# Modbus_RTU.net
KiCad netlist of a schematic drawn in Altium Designer
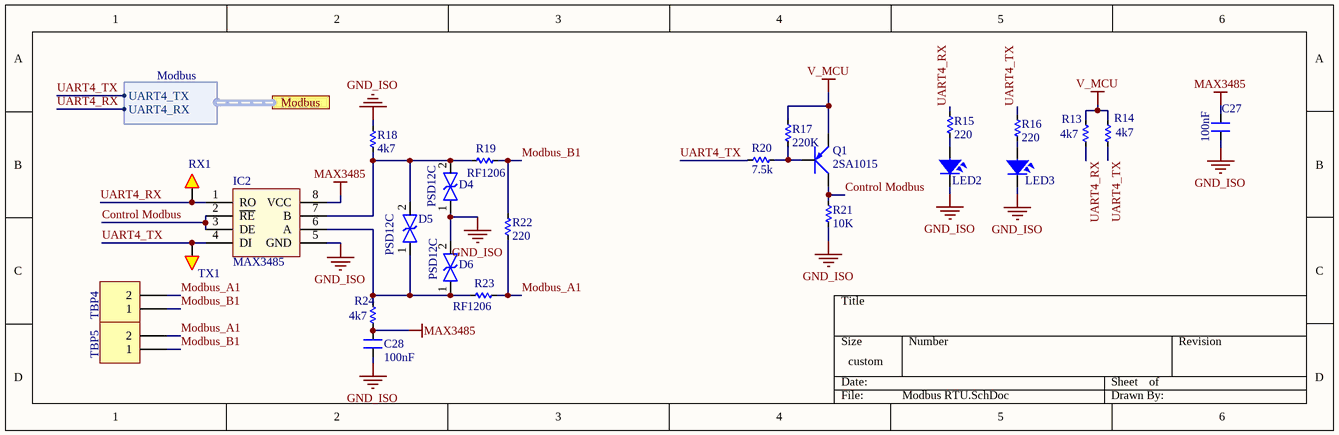
[diagram p0: Modbus RTU.SchDoc]

(export (version "E")
  (design (tool "Eeschema 10.0.6"))
  (components
    (comp (ref "B3")
      (value "RX1")
      (footprint "Test")
      (description "WR-PHD 2.54 mm Angled Socket Header")
      (fields
        (field (name "MANUFACTURER") "Würth Elektronik eiSos GmbH")
        (field (name "PARTNO") "613002143121")
        (field (name "CREATED BY") "Karrer Zheng")
      )
      (libsource (lib "Nichietsuvn") (part "Test"))
    )
    (comp (ref "B4")
      (value "TX1")
      (footprint "Test")
      (description "WR-PHD 2.54 mm Angled Socket Header")
      (fields
        (field (name "MANUFACTURER") "Würth Elektronik eiSos GmbH")
        (field (name "PARTNO") "613002143121")
        (field (name "CREATED BY") "Karrer Zheng")
      )
      (libsource (lib "Nichietsuvn") (part "Test"))
    )
    (comp (ref "C27") (value "100nF") (footprint "CN-SMD-0603") (libsource (lib "thu vien 3d") (part "CN")))
    (comp (ref "C28") (value "100nF") (footprint "CN-SMD-0603") (libsource (lib "thu vien 3d") (part "CN")))
    (comp (ref "D4")
      (value "PSD12C")
      (footprint "PSD12C")
      (description "diode tvs")
      (libsource (lib "Nichietsuvn") (part "PSD12C"))
    )
    (comp (ref "D5")
      (value "PSD12C")
      (footprint "PSD12C")
      (description "diode tvs")
      (libsource (lib "Nichietsuvn") (part "PSD12C"))
    )
    (comp (ref "D6")
      (value "PSD12C")
      (footprint "PSD12C")
      (description "diode tvs")
      (libsource (lib "Nichietsuvn") (part "PSD12C"))
    )
    (comp (ref "IC2")
      (value "MAX3485")
      (footprint "SO8")
      (description "RS232 - RS485 (Same sn75176)")
      (libsource (lib "thu vien 3d") (part "MAX485"))
    )
    (comp (ref "LED2")
      (value "LED")
      (footprint "LED-0805-Blue")
      (libsource (lib "thu vien 3d") (part "LED SMD"))
    )
    (comp (ref "LED3")
      (value "LED")
      (footprint "LED-0805-Blue")
      (libsource (lib "thu vien 3d") (part "LED SMD"))
    )
    (comp (ref "Q1")
      (value "2SA1015")
      (footprint "SOT23-321")
      (description "PNP 600mW, ECB")
      (libsource (lib "thu vien 3d") (part "2SA1015"))
    )
    (comp (ref "R13")
      (value "4k7")
      (footprint "RES-SMD-0603")
      (description "Resistor")
      (fields
        (field (name "MANUFACTURER") "Generic Components")
        (field (name "PUBLISHER") "Altium Hobart Technology Centre")
      )
      (libsource (lib "thu vien 3d") (part "Res-SMD"))
    )
    (comp (ref "R14")
      (value "4k7")
      (footprint "RES-SMD-0603")
      (description "Resistor")
      (fields
        (field (name "MANUFACTURER") "Generic Components")
        (field (name "PUBLISHER") "Altium Hobart Technology Centre")
      )
      (libsource (lib "thu vien 3d") (part "Res-SMD"))
    )
    (comp (ref "R15")
      (value "220")
      (footprint "RES-SMD-0603")
      (description "Resistor")
      (fields
        (field (name "MANUFACTURER") "Generic Components")
        (field (name "PUBLISHER") "Altium Hobart Technology Centre")
      )
      (libsource (lib "thu vien 3d") (part "Res-SMD"))
    )
    (comp (ref "R16")
      (value "220")
      (footprint "RES-SMD-0603")
      (description "Resistor")
      (fields
        (field (name "MANUFACTURER") "Generic Components")
        (field (name "PUBLISHER") "Altium Hobart Technology Centre")
      )
      (libsource (lib "thu vien 3d") (part "Res-SMD"))
    )
    (comp (ref "R17")
      (value "220K")
      (footprint "RES-SMD-0603")
      (description "Resistor")
      (fields
        (field (name "MANUFACTURER") "Generic Components")
        (field (name "PUBLISHER") "Altium Hobart Technology Centre")
      )
      (libsource (lib "thu vien 3d") (part "Res-SMD"))
    )
    (comp (ref "R18")
      (value "4k7")
      (footprint "RES-SMD-0603")
      (description "Resistor")
      (fields
        (field (name "MANUFACTURER") "Generic Components")
        (field (name "PUBLISHER") "Altium Hobart Technology Centre")
      )
      (libsource (lib "thu vien 3d") (part "Res-SMD"))
    )
    (comp (ref "R19")
      (value "RF1206")
      (footprint "RES-SMD-1206")
      (description "Resistor")
      (fields
        (field (name "MANUFACTURER") "Generic Components")
        (field (name "PUBLISHER") "Altium Hobart Technology Centre")
      )
      (libsource (lib "thu vien 3d") (part "Res-SMD"))
    )
    (comp (ref "R20")
      (value "7.5k")
      (footprint "RES-SMD-0603")
      (description "Resistor")
      (fields
        (field (name "MANUFACTURER") "Generic Components")
        (field (name "PUBLISHER") "Altium Hobart Technology Centre")
      )
      (libsource (lib "thu vien 3d") (part "Res-SMD"))
    )
    (comp (ref "R21")
      (value "10K")
      (footprint "RES-SMD-0603")
      (description "Resistor")
      (fields
        (field (name "MANUFACTURER") "Generic Components")
        (field (name "PUBLISHER") "Altium Hobart Technology Centre")
      )
      (libsource (lib "thu vien 3d") (part "Res-SMD"))
    )
    (comp (ref "R22")
      (value "220")
      (footprint "RES-SMD-0603")
      (description "Resistor")
      (fields
        (field (name "MANUFACTURER") "Generic Components")
        (field (name "PUBLISHER") "Altium Hobart Technology Centre")
      )
      (libsource (lib "thu vien 3d") (part "Res-SMD"))
    )
    (comp (ref "R23")
      (value "RF1206")
      (footprint "RES-SMD-1206")
      (description "Resistor")
      (fields
        (field (name "MANUFACTURER") "Generic Components")
        (field (name "PUBLISHER") "Altium Hobart Technology Centre")
      )
      (libsource (lib "thu vien 3d") (part "Res-SMD"))
    )
    (comp (ref "R24")
      (value "4k7")
      (footprint "RES-SMD-0603")
      (description "Resistor")
      (fields
        (field (name "MANUFACTURER") "Generic Components")
        (field (name "PUBLISHER") "Altium Hobart Technology Centre")
      )
      (libsource (lib "thu vien 3d") (part "Res-SMD"))
    )
    (comp (ref "TBP4")
      (value "WE-Terminal Blocks Plugable Type 691322310002")
      (footprint "Terminal_Blocks_Pluggable_Socket__Right_Angle__3.81_mm_Pitch__2_Position")
      (description "WR-TBL Terminal block - serie 322 - 3.81 mm")
      (libsource (lib "All Library") (part "Terminal_Blocks_Pluggable_Socket__Right_Angle__3.81_mm_Pitch__2_Position"))
    )
    (comp (ref "TBP5")
      (value "WE-Terminal Blocks Plugable Type 691322310002")
      (footprint "Terminal_Blocks_Pluggable_Socket__Right_Angle__3.81_mm_Pitch__2_Position")
      (description "WR-TBL Terminal block - serie 322 - 3.81 mm")
      (libsource (lib "All Library") (part "Terminal_Blocks_Pluggable_Socket__Right_Angle__3.81_mm_Pitch__2_Position"))
    )
  )
  (nets
    (net (code "2") (name "/Control Modbus") (class "Default")
      (node (ref "IC2") (pin "2") (pinfunction "~{RE}_2") (pintype "passive"))
      (node (ref "IC2") (pin "3") (pinfunction "DE_3") (pintype "passive"))
      (node (ref "Q1") (pin "2") (pinfunction "C_2") (pintype "passive"))
      (node (ref "R21") (pin "2") (pinfunction "2_2") (pintype "passive"))
    )
    (net (code "3") (name "/Modbus_A1") (class "Default")
      (node (ref "R22") (pin "2") (pinfunction "2_2") (pintype "passive"))
      (node (ref "R23") (pin "1") (pinfunction "1_1") (pintype "passive"))
      (node (ref "TBP4") (pin "2") (pinfunction "2_2") (pintype "passive"))
      (node (ref "TBP5") (pin "2") (pinfunction "2_2") (pintype "passive"))
    )
    (net (code "4") (name "/Modbus_B1") (class "Default")
      (node (ref "R19") (pin "1") (pinfunction "1_1") (pintype "passive"))
      (node (ref "R22") (pin "1") (pinfunction "1_1") (pintype "passive"))
      (node (ref "TBP4") (pin "1") (pinfunction "1_1") (pintype "passive"))
      (node (ref "TBP5") (pin "1") (pinfunction "1_1") (pintype "passive"))
    )
    (net (code "5") (name "/UART4_RX") (class "Default")
      (node (ref "B3") (pin "1") (pinfunction "1_1") (pintype "passive"))
      (node (ref "IC2") (pin "1") (pinfunction "RO_1") (pintype "passive"))
      (node (ref "R13") (pin "2") (pinfunction "2_2") (pintype "passive"))
      (node (ref "R15") (pin "1") (pinfunction "1_1") (pintype "passive"))
    )
    (net (code "6") (name "/UART4_TX") (class "Default")
      (node (ref "B4") (pin "1") (pinfunction "1_1") (pintype "passive"))
      (node (ref "IC2") (pin "4") (pinfunction "DI_4") (pintype "passive"))
      (node (ref "R14") (pin "2") (pinfunction "2_2") (pintype "passive"))
      (node (ref "R16") (pin "1") (pinfunction "1_1") (pintype "passive"))
      (node (ref "R20") (pin "1") (pinfunction "1_1") (pintype "passive"))
    )
    (net (code "8") (name "GND_ISO") (class "Default")
      (node (ref "C27") (pin "1") (pinfunction "1_1") (pintype "passive"))
      (node (ref "C28") (pin "2") (pinfunction "2_2") (pintype "passive"))
      (node (ref "D4") (pin "1") (pinfunction "1_1") (pintype "passive"))
      (node (ref "D6") (pin "2") (pinfunction "2_2") (pintype "passive"))
      (node (ref "IC2") (pin "5") (pinfunction "GND_5") (pintype "passive"))
      (node (ref "LED2") (pin "2") (pinfunction "2_2") (pintype "passive"))
      (node (ref "LED3") (pin "2") (pinfunction "2_2") (pintype "passive"))
      (node (ref "R18") (pin "1") (pinfunction "1_1") (pintype "passive"))
      (node (ref "R21") (pin "1") (pinfunction "1_1") (pintype "passive"))
    )
    (net (code "9") (name "MAX3485") (class "Default")
      (node (ref "C27") (pin "2") (pinfunction "2_2") (pintype "passive"))
      (node (ref "C28") (pin "1") (pinfunction "1_1") (pintype "passive"))
      (node (ref "IC2") (pin "8") (pinfunction "VCC_8") (pintype "passive"))
      (node (ref "R24") (pin "1") (pinfunction "1_1") (pintype "passive"))
    )
    (net (code "10") (name "Net-(IC2-A)") (class "Default")
      (node (ref "D5") (pin "1") (pinfunction "1_1") (pintype "passive"))
      (node (ref "D6") (pin "1") (pinfunction "1_1") (pintype "passive"))
      (node (ref "IC2") (pin "6") (pinfunction "A_6") (pintype "passive"))
      (node (ref "R23") (pin "2") (pinfunction "2_2") (pintype "passive"))
      (node (ref "R24") (pin "2") (pinfunction "2_2") (pintype "passive"))
    )
    (net (code "11") (name "Net-(IC2-B)") (class "Default")
      (node (ref "D4") (pin "2") (pinfunction "2_2") (pintype "passive"))
      (node (ref "D5") (pin "2") (pinfunction "2_2") (pintype "passive"))
      (node (ref "IC2") (pin "7") (pinfunction "B_7") (pintype "passive"))
      (node (ref "R18") (pin "2") (pinfunction "2_2") (pintype "passive"))
      (node (ref "R19") (pin "2") (pinfunction "2_2") (pintype "passive"))
    )
    (net (code "12") (name "Net-(LED2-Pad1)") (class "Default")
      (node (ref "LED2") (pin "1") (pinfunction "1_1") (pintype "passive"))
      (node (ref "R15") (pin "2") (pinfunction "2_2") (pintype "passive"))
    )
    (net (code "13") (name "Net-(LED3-Pad1)") (class "Default")
      (node (ref "LED3") (pin "1") (pinfunction "1_1") (pintype "passive"))
      (node (ref "R16") (pin "2") (pinfunction "2_2") (pintype "passive"))
    )
    (net (code "14") (name "Net-(Q1-B)") (class "Default")
      (node (ref "Q1") (pin "3") (pinfunction "B_3") (pintype "passive"))
      (node (ref "R17") (pin "1") (pinfunction "1_1") (pintype "passive"))
      (node (ref "R20") (pin "2") (pinfunction "2_2") (pintype "passive"))
    )
    (net (code "15") (name "V_MCU") (class "Default")
      (node (ref "Q1") (pin "1") (pinfunction "E_1") (pintype "passive"))
      (node (ref "R13") (pin "1") (pinfunction "1_1") (pintype "passive"))
      (node (ref "R14") (pin "1") (pinfunction "1_1") (pintype "passive"))
      (node (ref "R17") (pin "2") (pinfunction "2_2") (pintype "passive"))
    )
  )
)
